# vin_shunt.net
KiCad netlist of a schematic drawn in Altium Designer
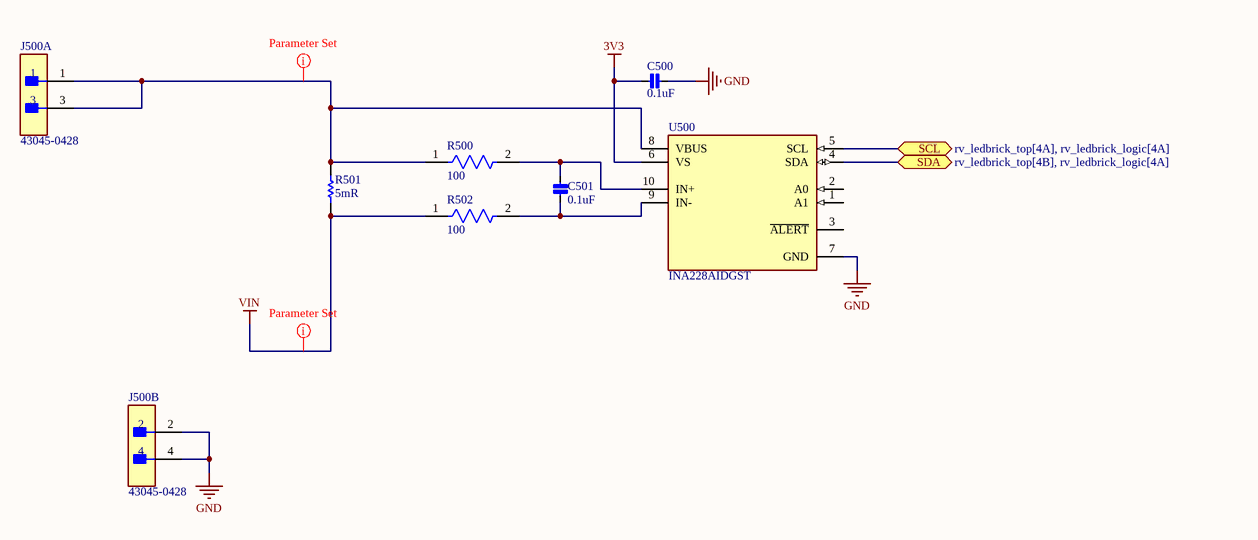
[diagram p0: vin_shunt.SchDoc]

(export (version "E")
  (design (tool "Eeschema 10.0.6"))
  (components
    (comp (ref "C500")
      (value "0.1uF")
      (footprint "FP-CL10-IPC_B")
      (description "Cap Ceramic 0.1uF 50V X7R 20% SMD 0603 125C Paper T/R")
      (fields (field (name "VOLTAGE") "50V") (field (name "Comment") "CAP 0.1uF 50V X7R 0603"))
      (libsource (lib "") (part "C-EU_1"))
    )
    (comp (ref "C501")
      (value "0.1uF")
      (footprint "FP-CL10-IPC_B")
      (description "Cap Ceramic 0.1uF 50V X7R 20% SMD 0603 125C Paper T/R")
      (fields (field (name "VOLTAGE") "50V") (field (name "Comment") "CAP 0.1uF 50V X7R 0603"))
      (libsource (lib "StackFoundry LLC") (part "C-EU"))
    )
    (comp (ref "J500")
      (value "43045-0428")
      (footprint "FP-43045-0428-MFG")
      (libsource (lib "StackFoundry LLC") (part "1621473add15499e993d6bbd36d0f06"))
    )
    (comp (ref "R500")
      (value "100")
      (footprint "FP-RC0603-0_55-MFG")
      (fields
        (field (name "POWER") "100mW")
        (field (name "TOLERANCE") "1%")
        (field (name "Comment") "100R 0603 1%")
      )
      (libsource (lib "StackFoundry LLC") (part "1029c3af85768c4190bb7ad29bc67b5"))
    )
    (comp (ref "R501")
      (value "5mR")
      (footprint "RESC7146X09N")
      (description "Res Metal Strip 2818 0.005 Ohm 1% 5W ±200ppm/°C Pad SMD Automotive T/R")
      (fields (field (name "TOLERANCE") "1%") (field (name "Comment") "0R005 HOXLR2817-5W-5MR-1%"))
      (libsource (lib "StackFoundry LLC") (part "RES"))
    )
    (comp (ref "R502")
      (value "100")
      (footprint "FP-RC0603-0_55-MFG")
      (fields
        (field (name "POWER") "100mW")
        (field (name "TOLERANCE") "1%")
        (field (name "Comment") "100R 0603 1%")
      )
      (libsource (lib "StackFoundry LLC") (part "1029c3af85768c4190bb7ad29bc67b5"))
    )
    (comp (ref "U500")
      (value "INA228AIDGST")
      (footprint "FP-DGS0010A-IPC_C")
      (description "Power Supply Support Circuit, Adjustable, 1 Channel, PDSO10")
      (libsource (lib "StackFoundry LLC") (part "1af3035f59f546649392dbf5608e80d"))
    )
  )
  (nets
    (net (code "1") (name "/SCL") (class "Default")
      (node (ref "U500") (pin "5") (pinfunction "SCL_5") (pintype "input"))
    )
    (net (code "2") (name "/SDA") (class "Default")
      (node (ref "U500") (pin "4") (pinfunction "SDA_4") (pintype "bidirectional"))
    )
    (net (code "3") (name "3V3") (class "Default")
      (node (ref "C500") (pin "1") (pinfunction "1_1") (pintype "passive"))
      (node (ref "U500") (pin "6") (pinfunction "VS_6") (pintype "power_in"))
    )
    (net (code "4") (name "GND") (class "Default")
      (node (ref "C500") (pin "2") (pinfunction "2_2") (pintype "passive"))
      (node (ref "J500") (pin "2") (pinfunction "2_2") (pintype "passive"))
      (node (ref "J500") (pin "4") (pinfunction "4_4") (pintype "passive"))
      (node (ref "U500") (pin "7") (pinfunction "GND_7") (pintype "power_in"))
    )
    (net (code "5") (name "Net-(U500-IN+)") (class "Default")
      (node (ref "C501") (pin "1") (pinfunction "1_1") (pintype "passive"))
      (node (ref "R500") (pin "2") (pinfunction "2_2") (pintype "passive"))
      (node (ref "U500") (pin "10") (pinfunction "IN+_10") (pintype "passive"))
    )
    (net (code "6") (name "Net-(U500-IN-)") (class "Default")
      (node (ref "C501") (pin "2") (pinfunction "2_2") (pintype "passive"))
      (node (ref "R502") (pin "2") (pinfunction "2_2") (pintype "passive"))
      (node (ref "U500") (pin "9") (pinfunction "IN-_9") (pintype "passive"))
    )
    (net (code "7") (name "Net-(U500-VBUS)") (class "Default")
      (node (ref "J500") (pin "1") (pinfunction "1_1") (pintype "passive"))
      (node (ref "J500") (pin "3") (pinfunction "3_3") (pintype "passive"))
      (node (ref "R500") (pin "1") (pinfunction "1_1") (pintype "passive"))
      (node (ref "R501") (pin "2") (pinfunction "2_2") (pintype "passive"))
      (node (ref "U500") (pin "8") (pinfunction "VBUS_8") (pintype "power_in"))
    )
    (net (code "8") (name "VIN") (class "Default")
      (node (ref "R501") (pin "1") (pinfunction "1_1") (pintype "passive"))
      (node (ref "R502") (pin "1") (pinfunction "1_1") (pintype "passive"))
    )
    (net (code "9") (name "unconnected-(U500-A0-Pad2)") (class "Default")
      (node (ref "U500") (pin "2") (pinfunction "A0_2") (pintype "input"))
    )
    (net (code "10") (name "unconnected-(U500-A1-Pad1)") (class "Default")
      (node (ref "U500") (pin "1") (pinfunction "A1_1") (pintype "input"))
    )
    (net (code "11") (name "unconnected-(U500-~{ALERT}-Pad3)") (class "Default")
      (node (ref "U500") (pin "3") (pinfunction "~{ALERT}_3") (pintype "open_collector"))
    )
  )
)
